# csa_extender_v1_0a.net
KiCad netlist of a schematic drawn in EAGLE
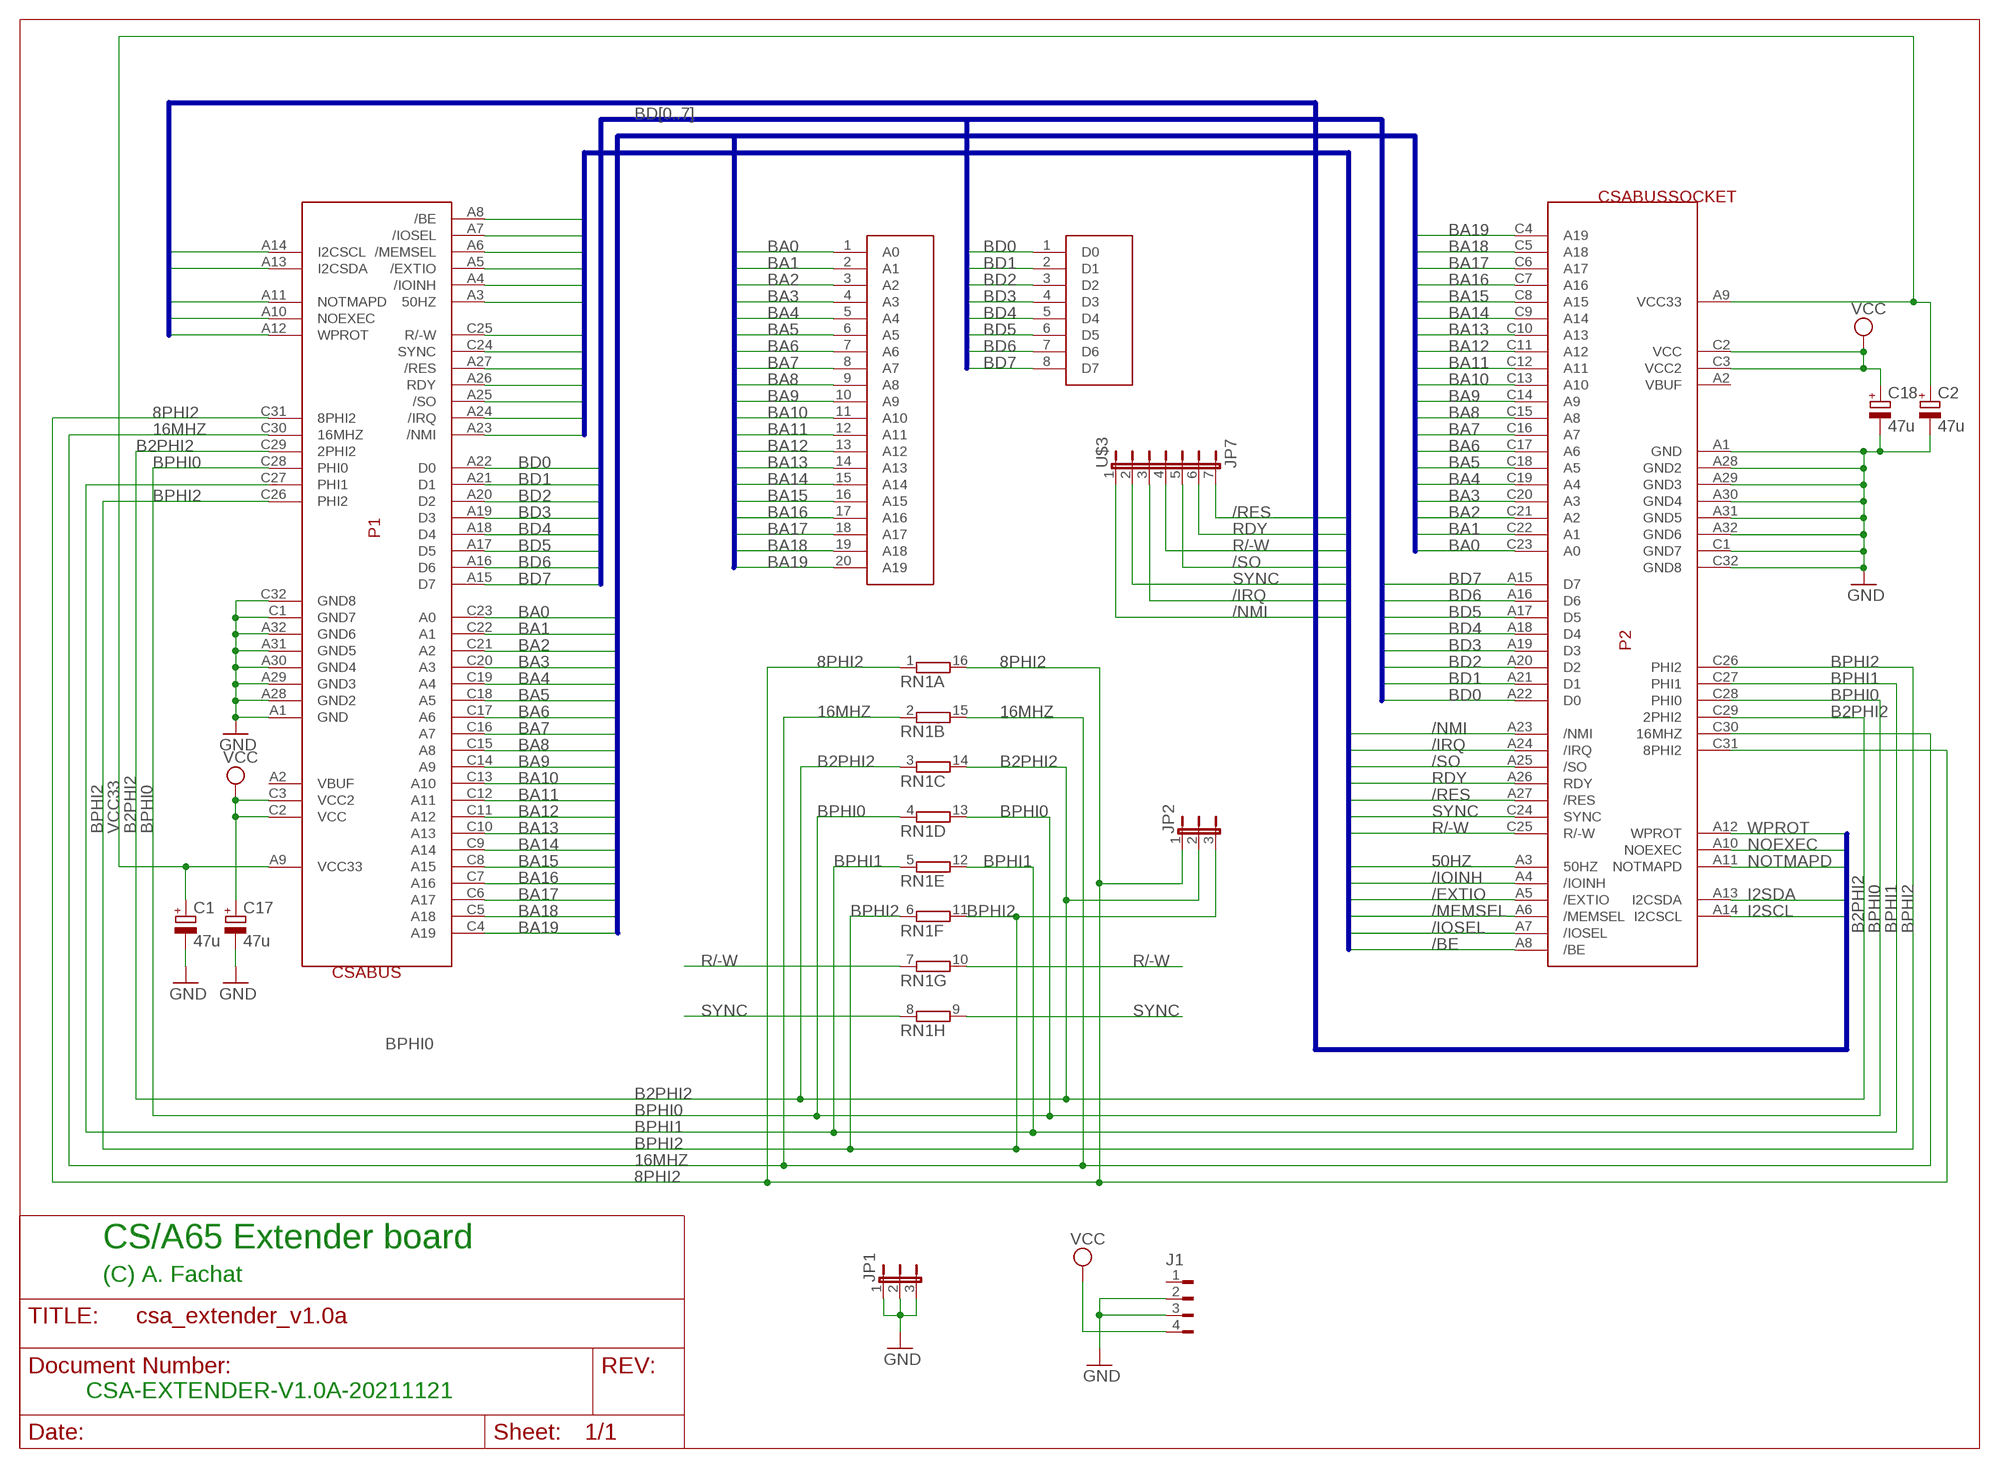
[diagram p0: schematic, sheet 1]

(export (version "E")
  (design (tool "Eeschema 10.0.6"))
  (components
    (comp (ref "C1")
      (value "47u")
      (footprint "eagle-import:E2,5-5")
      (libsource (lib "eagle-import") (part "CPOL-EUE2.5-5"))
    )
    (comp (ref "C2")
      (value "47u")
      (footprint "eagle-import:E2,5-5")
      (libsource (lib "eagle-import") (part "CPOL-EUE2.5-5"))
    )
    (comp (ref "C17")
      (value "47u")
      (footprint "eagle-import:E2,5-5")
      (libsource (lib "eagle-import") (part "CPOL-EUE2.5-5"))
    )
    (comp (ref "C18")
      (value "47u")
      (footprint "eagle-import:E2,5-5")
      (libsource (lib "eagle-import") (part "CPOL-EUE2.5-5"))
    )
    (comp (ref "J1")
      (value "FLOP-4W827001")
      (footprint "eagle-import:827001")
      (libsource (lib "eagle-import") (part "FLOP-4W827001"))
    )
    (comp (ref "JP1")
      (value "JP2E")
      (footprint "eagle-import:JP2")
      (libsource (lib "eagle-import") (part "JP2E"))
    )
    (comp (ref "JP2")
      (value "JP2E")
      (footprint "eagle-import:JP2")
      (libsource (lib "eagle-import") (part "JP2E"))
    )
    (comp (ref "P1")
      (value "CSABUS")
      (footprint "eagle-import:CSABUS")
      (libsource (lib "eagle-import") (part "CSABUS"))
    )
    (comp (ref "P2")
      (value "CSABUSSOCKET")
      (footprint "eagle-import:CSABUSSOCK")
      (libsource (lib "eagle-import") (part "CSABUSSOCKET"))
    )
    (comp (ref "RN1")
      (value "8R-N")
      (footprint "eagle-import:DIL16")
      (libsource (lib "eagle-import") (part "8R-N"))
    )
    (comp (ref "U$1")
      (value "JA0-19")
      (footprint "eagle-import:A0-19")
      (libsource (lib "eagle-import") (part "JA0-19"))
    )
    (comp (ref "U$2")
      (value "JD0-7")
      (footprint "eagle-import:D0-7")
      (libsource (lib "eagle-import") (part "JD0-7"))
    )
    (comp (ref "U$3")
      (value "JP7")
      (footprint "eagle-import:JP7")
      (libsource (lib "eagle-import") (part "JP7"))
    )
  )
  (nets
    (net (code "1") (name "/8PHI2") (class "Default")
      (node (ref "JP2") (pin "1") (pinfunction "1_1") (pintype "passive"))
      (node (ref "P1") (pin "C31") (pinfunction "8PHI2_C31") (pintype "bidirectional"))
      (node (ref "P2") (pin "C31") (pinfunction "8PHI2_C31") (pintype "bidirectional"))
      (node (ref "RN1") (pin "1") (pinfunction "1_1") (pintype "passive"))
      (node (ref "RN1") (pin "16") (pinfunction "2_16") (pintype "passive"))
    )
    (net (code "2") (name "/16MHZ") (class "Default")
      (node (ref "P1") (pin "C30") (pinfunction "16MHZ_C30") (pintype "bidirectional"))
      (node (ref "P2") (pin "C30") (pinfunction "16MHZ_C30") (pintype "bidirectional"))
      (node (ref "RN1") (pin "15") (pinfunction "2_15") (pintype "passive"))
      (node (ref "RN1") (pin "2") (pinfunction "1_2") (pintype "passive"))
    )
    (net (code "3") (name "/50HZ") (class "Default")
      (node (ref "P1") (pin "A3") (pinfunction "50HZ_A3") (pintype "bidirectional"))
      (node (ref "P2") (pin "A3") (pinfunction "50HZ_A3") (pintype "bidirectional"))
    )
    (net (code "4") (name "/B2PHI2") (class "Default")
      (node (ref "JP2") (pin "2") (pinfunction "2_2") (pintype "passive"))
      (node (ref "P1") (pin "C29") (pinfunction "2PHI2_C29") (pintype "bidirectional"))
      (node (ref "P2") (pin "C29") (pinfunction "2PHI2_C29") (pintype "bidirectional"))
      (node (ref "RN1") (pin "14") (pinfunction "2_14") (pintype "passive"))
      (node (ref "RN1") (pin "3") (pinfunction "1_3") (pintype "passive"))
    )
    (net (code "5") (name "/BA0") (class "Default")
      (node (ref "P1") (pin "C23") (pinfunction "A0_C23") (pintype "bidirectional"))
      (node (ref "P2") (pin "C23") (pinfunction "A0_C23") (pintype "bidirectional"))
      (node (ref "U$1") (pin "1") (pinfunction "A0_1") (pintype "bidirectional"))
    )
    (net (code "6") (name "/BA1") (class "Default")
      (node (ref "P1") (pin "C22") (pinfunction "A1_C22") (pintype "bidirectional"))
      (node (ref "P2") (pin "C22") (pinfunction "A1_C22") (pintype "bidirectional"))
      (node (ref "U$1") (pin "2") (pinfunction "A1_2") (pintype "bidirectional"))
    )
    (net (code "7") (name "/BA2") (class "Default")
      (node (ref "P1") (pin "C21") (pinfunction "A2_C21") (pintype "bidirectional"))
      (node (ref "P2") (pin "C21") (pinfunction "A2_C21") (pintype "bidirectional"))
      (node (ref "U$1") (pin "3") (pinfunction "A2_3") (pintype "bidirectional"))
    )
    (net (code "8") (name "/BA3") (class "Default")
      (node (ref "P1") (pin "C20") (pinfunction "A3_C20") (pintype "bidirectional"))
      (node (ref "P2") (pin "C20") (pinfunction "A3_C20") (pintype "bidirectional"))
      (node (ref "U$1") (pin "4") (pinfunction "A3_4") (pintype "bidirectional"))
    )
    (net (code "9") (name "/BA4") (class "Default")
      (node (ref "P1") (pin "C19") (pinfunction "A4_C19") (pintype "bidirectional"))
      (node (ref "P2") (pin "C19") (pinfunction "A4_C19") (pintype "bidirectional"))
      (node (ref "U$1") (pin "5") (pinfunction "A4_5") (pintype "bidirectional"))
    )
    (net (code "10") (name "/BA5") (class "Default")
      (node (ref "P1") (pin "C18") (pinfunction "A5_C18") (pintype "bidirectional"))
      (node (ref "P2") (pin "C18") (pinfunction "A5_C18") (pintype "bidirectional"))
      (node (ref "U$1") (pin "6") (pinfunction "A5_6") (pintype "bidirectional"))
    )
    (net (code "11") (name "/BA6") (class "Default")
      (node (ref "P1") (pin "C17") (pinfunction "A6_C17") (pintype "bidirectional"))
      (node (ref "P2") (pin "C17") (pinfunction "A6_C17") (pintype "bidirectional"))
      (node (ref "U$1") (pin "7") (pinfunction "A6_7") (pintype "bidirectional"))
    )
    (net (code "12") (name "/BA7") (class "Default")
      (node (ref "P1") (pin "C16") (pinfunction "A7_C16") (pintype "bidirectional"))
      (node (ref "P2") (pin "C16") (pinfunction "A7_C16") (pintype "bidirectional"))
      (node (ref "U$1") (pin "8") (pinfunction "A7_8") (pintype "bidirectional"))
    )
    (net (code "13") (name "/BA8") (class "Default")
      (node (ref "P1") (pin "C15") (pinfunction "A8_C15") (pintype "bidirectional"))
      (node (ref "P2") (pin "C15") (pinfunction "A8_C15") (pintype "bidirectional"))
      (node (ref "U$1") (pin "9") (pinfunction "A8_9") (pintype "bidirectional"))
    )
    (net (code "14") (name "/BA9") (class "Default")
      (node (ref "P1") (pin "C14") (pinfunction "A9_C14") (pintype "bidirectional"))
      (node (ref "P2") (pin "C14") (pinfunction "A9_C14") (pintype "bidirectional"))
      (node (ref "U$1") (pin "10") (pinfunction "A9_10") (pintype "bidirectional"))
    )
    (net (code "15") (name "/BA10") (class "Default")
      (node (ref "P1") (pin "C13") (pinfunction "A10_C13") (pintype "bidirectional"))
      (node (ref "P2") (pin "C13") (pinfunction "A10_C13") (pintype "bidirectional"))
      (node (ref "U$1") (pin "11") (pinfunction "A10_11") (pintype "bidirectional"))
    )
    (net (code "16") (name "/BA11") (class "Default")
      (node (ref "P1") (pin "C12") (pinfunction "A11_C12") (pintype "bidirectional"))
      (node (ref "P2") (pin "C12") (pinfunction "A11_C12") (pintype "bidirectional"))
      (node (ref "U$1") (pin "12") (pinfunction "A11_12") (pintype "bidirectional"))
    )
    (net (code "17") (name "/BA12") (class "Default")
      (node (ref "P1") (pin "C11") (pinfunction "A12_C11") (pintype "bidirectional"))
      (node (ref "P2") (pin "C11") (pinfunction "A12_C11") (pintype "bidirectional"))
      (node (ref "U$1") (pin "13") (pinfunction "A12_13") (pintype "bidirectional"))
    )
    (net (code "18") (name "/BA13") (class "Default")
      (node (ref "P1") (pin "C10") (pinfunction "A13_C10") (pintype "bidirectional"))
      (node (ref "P2") (pin "C10") (pinfunction "A13_C10") (pintype "bidirectional"))
      (node (ref "U$1") (pin "14") (pinfunction "A13_14") (pintype "bidirectional"))
    )
    (net (code "19") (name "/BA14") (class "Default")
      (node (ref "P1") (pin "C9") (pinfunction "A14_C9") (pintype "bidirectional"))
      (node (ref "P2") (pin "C9") (pinfunction "A14_C9") (pintype "bidirectional"))
      (node (ref "U$1") (pin "15") (pinfunction "A14_15") (pintype "bidirectional"))
    )
    (net (code "20") (name "/BA15") (class "Default")
      (node (ref "P1") (pin "C8") (pinfunction "A15_C8") (pintype "bidirectional"))
      (node (ref "P2") (pin "C8") (pinfunction "A15_C8") (pintype "bidirectional"))
      (node (ref "U$1") (pin "16") (pinfunction "A15_16") (pintype "bidirectional"))
    )
    (net (code "21") (name "/BA16") (class "Default")
      (node (ref "P1") (pin "C7") (pinfunction "A16_C7") (pintype "bidirectional"))
      (node (ref "P2") (pin "C7") (pinfunction "A16_C7") (pintype "bidirectional"))
      (node (ref "U$1") (pin "17") (pinfunction "A16_17") (pintype "bidirectional"))
    )
    (net (code "22") (name "/BA17") (class "Default")
      (node (ref "P1") (pin "C6") (pinfunction "A17_C6") (pintype "bidirectional"))
      (node (ref "P2") (pin "C6") (pinfunction "A17_C6") (pintype "bidirectional"))
      (node (ref "U$1") (pin "18") (pinfunction "A17_18") (pintype "bidirectional"))
    )
    (net (code "23") (name "/BA18") (class "Default")
      (node (ref "P1") (pin "C5") (pinfunction "A18_C5") (pintype "bidirectional"))
      (node (ref "P2") (pin "C5") (pinfunction "A18_C5") (pintype "bidirectional"))
      (node (ref "U$1") (pin "19") (pinfunction "A18_19") (pintype "bidirectional"))
    )
    (net (code "24") (name "/BA19") (class "Default")
      (node (ref "P1") (pin "C4") (pinfunction "A19_C4") (pintype "bidirectional"))
      (node (ref "P2") (pin "C4") (pinfunction "A19_C4") (pintype "bidirectional"))
      (node (ref "U$1") (pin "20") (pinfunction "A19_20") (pintype "bidirectional"))
    )
    (net (code "25") (name "/BD0") (class "Default")
      (node (ref "P1") (pin "A22") (pinfunction "D0_A22") (pintype "bidirectional"))
      (node (ref "P2") (pin "A22") (pinfunction "D0_A22") (pintype "bidirectional"))
      (node (ref "U$2") (pin "1") (pinfunction "D0_1") (pintype "bidirectional"))
    )
    (net (code "26") (name "/BD1") (class "Default")
      (node (ref "P1") (pin "A21") (pinfunction "D1_A21") (pintype "bidirectional"))
      (node (ref "P2") (pin "A21") (pinfunction "D1_A21") (pintype "bidirectional"))
      (node (ref "U$2") (pin "2") (pinfunction "D1_2") (pintype "bidirectional"))
    )
    (net (code "27") (name "/BD2") (class "Default")
      (node (ref "P1") (pin "A20") (pinfunction "D2_A20") (pintype "bidirectional"))
      (node (ref "P2") (pin "A20") (pinfunction "D2_A20") (pintype "bidirectional"))
      (node (ref "U$2") (pin "3") (pinfunction "D2_3") (pintype "bidirectional"))
    )
    (net (code "28") (name "/BD3") (class "Default")
      (node (ref "P1") (pin "A19") (pinfunction "D3_A19") (pintype "bidirectional"))
      (node (ref "P2") (pin "A19") (pinfunction "D3_A19") (pintype "bidirectional"))
      (node (ref "U$2") (pin "4") (pinfunction "D3_4") (pintype "bidirectional"))
    )
    (net (code "29") (name "/BD4") (class "Default")
      (node (ref "P1") (pin "A18") (pinfunction "D4_A18") (pintype "bidirectional"))
      (node (ref "P2") (pin "A18") (pinfunction "D4_A18") (pintype "bidirectional"))
      (node (ref "U$2") (pin "5") (pinfunction "D4_5") (pintype "bidirectional"))
    )
    (net (code "30") (name "/BD5") (class "Default")
      (node (ref "P1") (pin "A17") (pinfunction "D5_A17") (pintype "bidirectional"))
      (node (ref "P2") (pin "A17") (pinfunction "D5_A17") (pintype "bidirectional"))
      (node (ref "U$2") (pin "6") (pinfunction "D5_6") (pintype "bidirectional"))
    )
    (net (code "31") (name "/BD6") (class "Default")
      (node (ref "P1") (pin "A16") (pinfunction "D6_A16") (pintype "bidirectional"))
      (node (ref "P2") (pin "A16") (pinfunction "D6_A16") (pintype "bidirectional"))
      (node (ref "U$2") (pin "7") (pinfunction "D6_7") (pintype "bidirectional"))
    )
    (net (code "32") (name "/BD7") (class "Default")
      (node (ref "P1") (pin "A15") (pinfunction "D7_A15") (pintype "bidirectional"))
      (node (ref "P2") (pin "A15") (pinfunction "D7_A15") (pintype "bidirectional"))
      (node (ref "U$2") (pin "8") (pinfunction "D7_8") (pintype "bidirectional"))
    )
    (net (code "34") (name "/BPHI0") (class "Default")
      (node (ref "P1") (pin "C28") (pinfunction "PHI0_C28") (pintype "bidirectional"))
      (node (ref "P2") (pin "C28") (pinfunction "PHI0_C28") (pintype "bidirectional"))
      (node (ref "RN1") (pin "13") (pinfunction "2_13") (pintype "passive"))
      (node (ref "RN1") (pin "4") (pinfunction "1_4") (pintype "passive"))
    )
    (net (code "35") (name "/BPHI1") (class "Default")
      (node (ref "P1") (pin "C27") (pinfunction "PHI1_C27") (pintype "bidirectional"))
      (node (ref "P2") (pin "C27") (pinfunction "PHI1_C27") (pintype "bidirectional"))
      (node (ref "RN1") (pin "12") (pinfunction "2_12") (pintype "passive"))
      (node (ref "RN1") (pin "5") (pinfunction "1_5") (pintype "passive"))
    )
    (net (code "36") (name "/BPHI2") (class "Default")
      (node (ref "JP2") (pin "3") (pinfunction "3_3") (pintype "passive"))
      (node (ref "P1") (pin "C26") (pinfunction "PHI2_C26") (pintype "bidirectional"))
      (node (ref "P2") (pin "C26") (pinfunction "PHI2_C26") (pintype "bidirectional"))
      (node (ref "RN1") (pin "11") (pinfunction "2_11") (pintype "passive"))
      (node (ref "RN1") (pin "6") (pinfunction "1_6") (pintype "passive"))
    )
    (net (code "37") (name "/I2SCL") (class "Default")
      (node (ref "P1") (pin "A14") (pinfunction "I2CSCL_A14") (pintype "bidirectional"))
      (node (ref "P2") (pin "A14") (pinfunction "I2CSCL_A14") (pintype "bidirectional"))
    )
    (net (code "38") (name "/I2SDA") (class "Default")
      (node (ref "P1") (pin "A13") (pinfunction "I2CSDA_A13") (pintype "bidirectional"))
      (node (ref "P2") (pin "A13") (pinfunction "I2CSDA_A13") (pintype "bidirectional"))
    )
    (net (code "39") (name "/NOEXEC") (class "Default")
      (node (ref "P1") (pin "A10") (pinfunction "NOEXEC_A10") (pintype "bidirectional"))
      (node (ref "P2") (pin "A10") (pinfunction "NOEXEC_A10") (pintype "bidirectional"))
    )
    (net (code "40") (name "/NOTMAPD") (class "Default")
      (node (ref "P1") (pin "A11") (pinfunction "NOTMAPD_A11") (pintype "bidirectional"))
      (node (ref "P2") (pin "A11") (pinfunction "NOTMAPD_A11") (pintype "bidirectional"))
    )
    (net (code "41") (name "/RDY") (class "Default")
      (node (ref "P1") (pin "A26") (pinfunction "RDY_A26") (pintype "bidirectional"))
      (node (ref "P2") (pin "A26") (pinfunction "RDY_A26") (pintype "bidirectional"))
      (node (ref "U$3") (pin "6") (pinfunction "6_6") (pintype "passive"))
    )
    (net (code "42") (name "/R{slash}-W") (class "Default")
      (node (ref "P1") (pin "C25") (pinfunction "R/-W_C25") (pintype "bidirectional"))
      (node (ref "P2") (pin "C25") (pinfunction "R/-W_C25") (pintype "bidirectional"))
      (node (ref "RN1") (pin "10") (pinfunction "2_10") (pintype "passive"))
      (node (ref "RN1") (pin "7") (pinfunction "1_7") (pintype "passive"))
      (node (ref "U$3") (pin "4") (pinfunction "4_4") (pintype "passive"))
    )
    (net (code "43") (name "/SYNC") (class "Default")
      (node (ref "P1") (pin "C24") (pinfunction "SYNC_C24") (pintype "bidirectional"))
      (node (ref "P2") (pin "C24") (pinfunction "SYNC_C24") (pintype "bidirectional"))
      (node (ref "RN1") (pin "8") (pinfunction "1_8") (pintype "passive"))
      (node (ref "RN1") (pin "9") (pinfunction "2_9") (pintype "passive"))
      (node (ref "U$3") (pin "2") (pinfunction "2_2") (pintype "passive"))
    )
    (net (code "44") (name "/VCC33") (class "Default")
      (node (ref "C1") (pin "+") (pinfunction "+_+") (pintype "passive"))
      (node (ref "C2") (pin "+") (pinfunction "+_+") (pintype "passive"))
      (node (ref "P1") (pin "A9") (pinfunction "VCC33_A9") (pintype "bidirectional"))
      (node (ref "P2") (pin "A9") (pinfunction "VCC33_A9") (pintype "bidirectional"))
    )
    (net (code "45") (name "/WPROT") (class "Default")
      (node (ref "P1") (pin "A12") (pinfunction "WPROT_A12") (pintype "bidirectional"))
      (node (ref "P2") (pin "A12") (pinfunction "WPROT_A12") (pintype "bidirectional"))
    )
    (net (code "46") (name "/{slash}BE") (class "Default")
      (node (ref "P1") (pin "A8") (pinfunction "/BE_A8") (pintype "bidirectional"))
      (node (ref "P2") (pin "A8") (pinfunction "/BE_A8") (pintype "bidirectional"))
    )
    (net (code "47") (name "/{slash}EXTIO") (class "Default")
      (node (ref "P1") (pin "A5") (pinfunction "/EXTIO_A5") (pintype "bidirectional"))
      (node (ref "P2") (pin "A5") (pinfunction "/EXTIO_A5") (pintype "bidirectional"))
    )
    (net (code "48") (name "/{slash}IOINH") (class "Default")
      (node (ref "P1") (pin "A4") (pinfunction "/IOINH_A4") (pintype "bidirectional"))
      (node (ref "P2") (pin "A4") (pinfunction "/IOINH_A4") (pintype "bidirectional"))
    )
    (net (code "49") (name "/{slash}IOSEL") (class "Default")
      (node (ref "P1") (pin "A7") (pinfunction "/IOSEL_A7") (pintype "bidirectional"))
      (node (ref "P2") (pin "A7") (pinfunction "/IOSEL_A7") (pintype "bidirectional"))
    )
    (net (code "50") (name "/{slash}IRQ") (class "Default")
      (node (ref "P1") (pin "A24") (pinfunction "/IRQ_A24") (pintype "bidirectional"))
      (node (ref "P2") (pin "A24") (pinfunction "/IRQ_A24") (pintype "bidirectional"))
      (node (ref "U$3") (pin "3") (pinfunction "3_3") (pintype "passive"))
    )
    (net (code "51") (name "/{slash}MEMSEL") (class "Default")
      (node (ref "P1") (pin "A6") (pinfunction "/MEMSEL_A6") (pintype "bidirectional"))
      (node (ref "P2") (pin "A6") (pinfunction "/MEMSEL_A6") (pintype "bidirectional"))
    )
    (net (code "52") (name "/{slash}NMI") (class "Default")
      (node (ref "P1") (pin "A23") (pinfunction "/NMI_A23") (pintype "bidirectional"))
      (node (ref "P2") (pin "A23") (pinfunction "/NMI_A23") (pintype "bidirectional"))
      (node (ref "U$3") (pin "1") (pinfunction "1_1") (pintype "passive"))
    )
    (net (code "53") (name "/{slash}RES") (class "Default")
      (node (ref "P1") (pin "A27") (pinfunction "/RES_A27") (pintype "bidirectional"))
      (node (ref "P2") (pin "A27") (pinfunction "/RES_A27") (pintype "bidirectional"))
      (node (ref "U$3") (pin "7") (pinfunction "7_7") (pintype "passive"))
    )
    (net (code "54") (name "/{slash}SO") (class "Default")
      (node (ref "P1") (pin "A25") (pinfunction "/SO_A25") (pintype "bidirectional"))
      (node (ref "P2") (pin "A25") (pinfunction "/SO_A25") (pintype "bidirectional"))
      (node (ref "U$3") (pin "5") (pinfunction "5_5") (pintype "passive"))
    )
    (net (code "55") (name "GND") (class "Default")
      (node (ref "C1") (pin "-") (pinfunction "-_-") (pintype "passive"))
      (node (ref "C17") (pin "-") (pinfunction "-_-") (pintype "passive"))
      (node (ref "C18") (pin "-") (pinfunction "-_-") (pintype "passive"))
      (node (ref "C2") (pin "-") (pinfunction "-_-") (pintype "passive"))
      (node (ref "J1") (pin "2") (pinfunction "2_2") (pintype "passive"))
      (node (ref "J1") (pin "3") (pinfunction "3_3") (pintype "passive"))
      (node (ref "JP1") (pin "1") (pinfunction "1_1") (pintype "passive"))
      (node (ref "JP1") (pin "2") (pinfunction "2_2") (pintype "passive"))
      (node (ref "JP1") (pin "3") (pinfunction "3_3") (pintype "passive"))
      (node (ref "P1") (pin "A1") (pinfunction "GND_A1") (pintype "bidirectional"))
      (node (ref "P1") (pin "A28") (pinfunction "GND2_A28") (pintype "bidirectional"))
      (node (ref "P1") (pin "A29") (pinfunction "GND3_A29") (pintype "bidirectional"))
      (node (ref "P1") (pin "A30") (pinfunction "GND4_A30") (pintype "bidirectional"))
      (node (ref "P1") (pin "A31") (pinfunction "GND5_A31") (pintype "bidirectional"))
      (node (ref "P1") (pin "A32") (pinfunction "GND6_A32") (pintype "bidirectional"))
      (node (ref "P1") (pin "C1") (pinfunction "GND7_C1") (pintype "bidirectional"))
      (node (ref "P1") (pin "C32") (pinfunction "GND8_C32") (pintype "bidirectional"))
      (node (ref "P2") (pin "A1") (pinfunction "GND_A1") (pintype "bidirectional"))
      (node (ref "P2") (pin "A28") (pinfunction "GND2_A28") (pintype "bidirectional"))
      (node (ref "P2") (pin "A29") (pinfunction "GND3_A29") (pintype "bidirectional"))
      (node (ref "P2") (pin "A30") (pinfunction "GND4_A30") (pintype "bidirectional"))
      (node (ref "P2") (pin "A31") (pinfunction "GND5_A31") (pintype "bidirectional"))
      (node (ref "P2") (pin "A32") (pinfunction "GND6_A32") (pintype "bidirectional"))
      (node (ref "P2") (pin "C1") (pinfunction "GND7_C1") (pintype "bidirectional"))
      (node (ref "P2") (pin "C32") (pinfunction "GND8_C32") (pintype "bidirectional"))
    )
    (net (code "56") (name "VCC") (class "Default")
      (node (ref "C17") (pin "+") (pinfunction "+_+") (pintype "passive"))
      (node (ref "C18") (pin "+") (pinfunction "+_+") (pintype "passive"))
      (node (ref "J1") (pin "4") (pinfunction "4_4") (pintype "passive"))
      (node (ref "P1") (pin "C2") (pinfunction "VCC_C2") (pintype "bidirectional"))
      (node (ref "P1") (pin "C3") (pinfunction "VCC2_C3") (pintype "bidirectional"))
      (node (ref "P2") (pin "C2") (pinfunction "VCC_C2") (pintype "bidirectional"))
      (node (ref "P2") (pin "C3") (pinfunction "VCC2_C3") (pintype "bidirectional"))
    )
    (net (code "57") (name "unconnected-(J1-Pad1)") (class "Default")
      (node (ref "J1") (pin "1") (pinfunction "1_1") (pintype "passive"))
    )
    (net (code "58") (name "unconnected-(P1-VBUF-PadA2)") (class "Default")
      (node (ref "P1") (pin "A2") (pinfunction "VBUF_A2") (pintype "bidirectional"))
    )
    (net (code "59") (name "unconnected-(P2-VBUF-PadA2)") (class "Default")
      (node (ref "P2") (pin "A2") (pinfunction "VBUF_A2") (pintype "bidirectional"))
    )
  )
)
